# placa2caras_CTO4.net
KiCad netlist of a schematic drawn in EAGLE
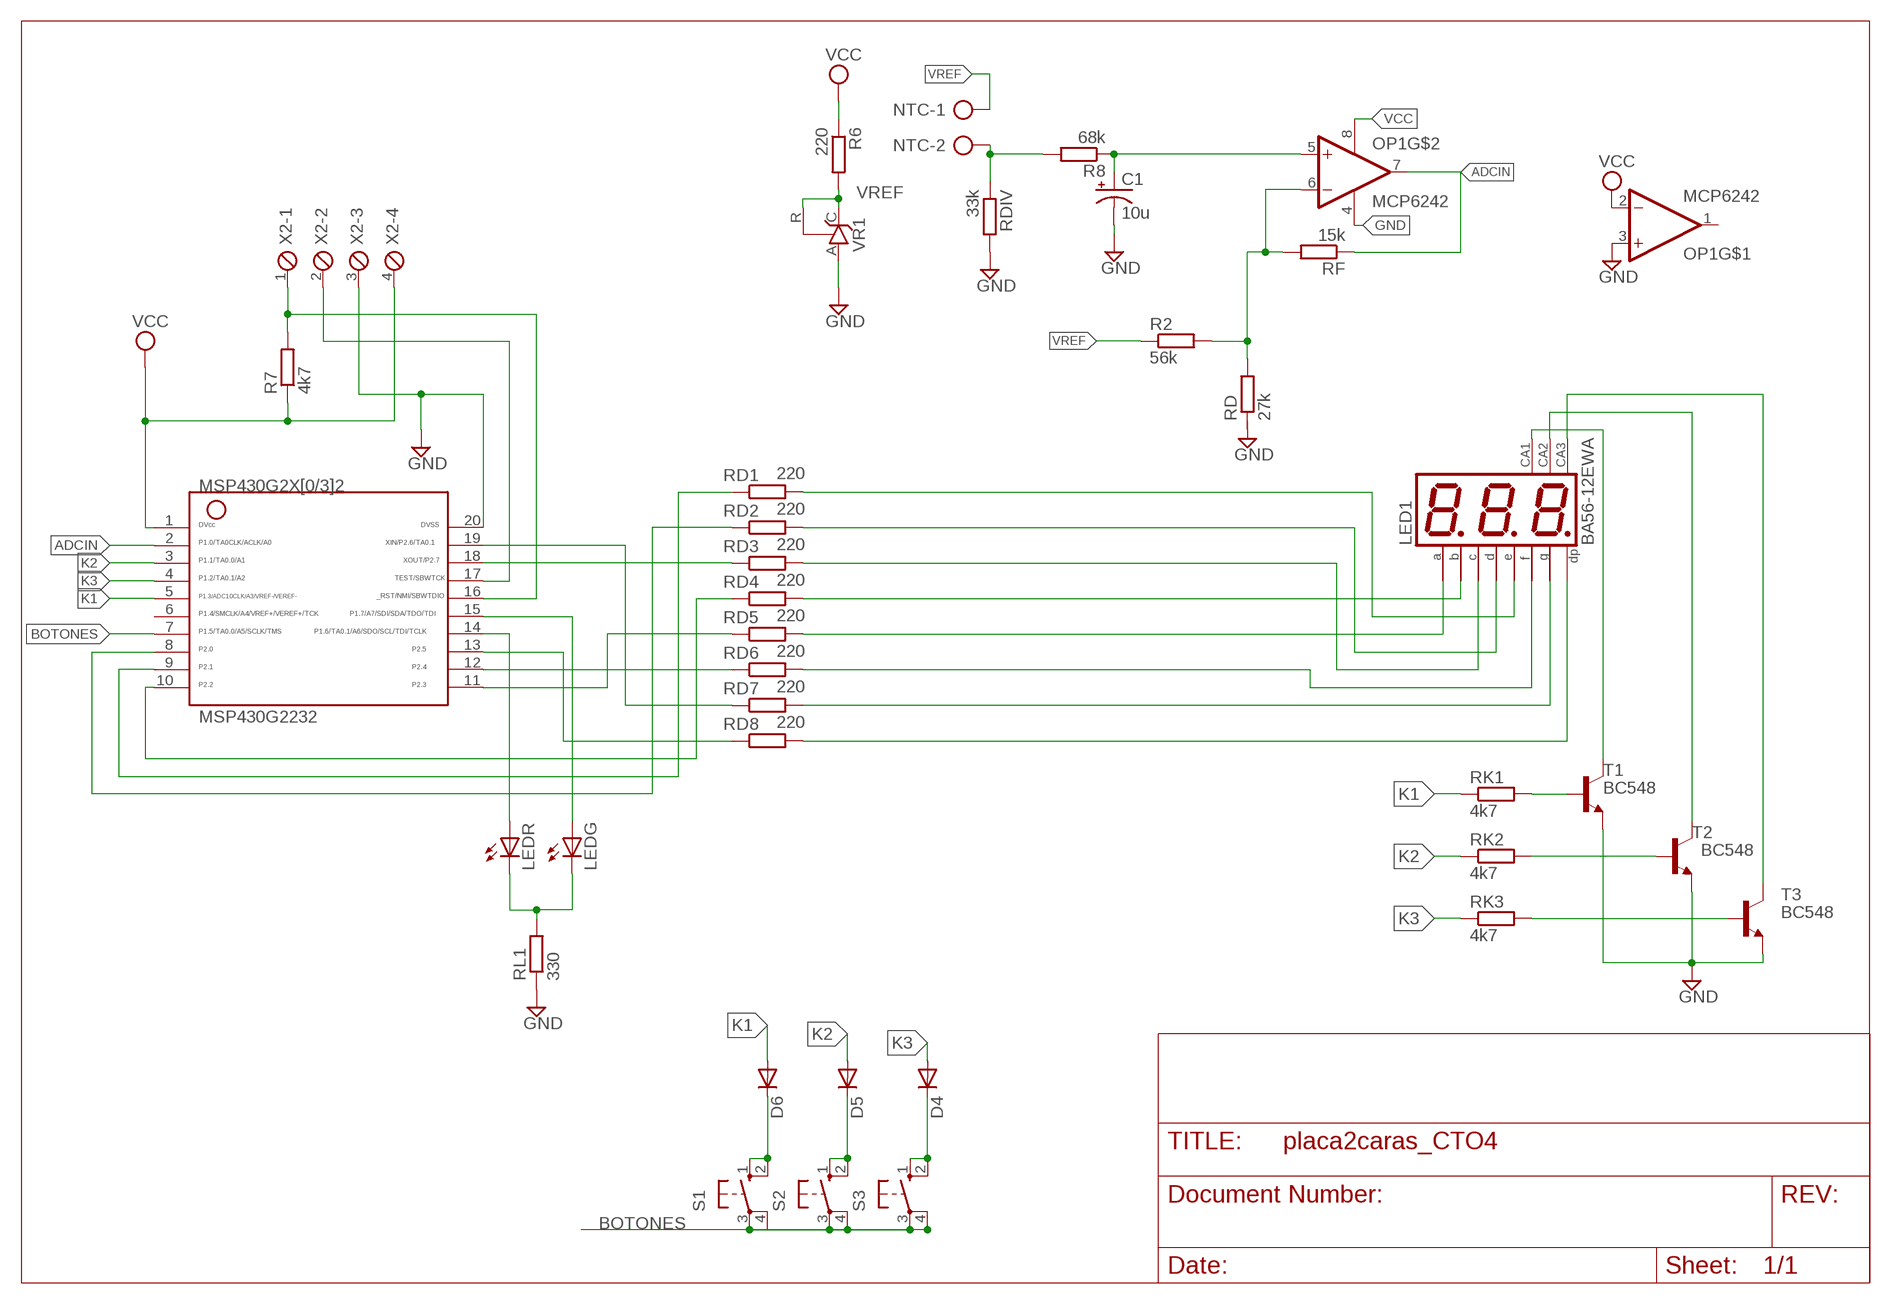
[diagram p0: schematic, sheet 1]

(export (version "E")
  (design (tool "Eeschema 10.0.6"))
  (components
    (comp (ref "C1")
      (value "10u")
      (footprint "eagle-import:E2,5-6E")
      (libsource (lib "eagle-import") (part "CPOL-USE2,5-6E"))
    )
    (comp (ref "D4")
      (value "1N4148DO35-10")
      (footprint "eagle-import:DO35-10")
      (libsource (lib "eagle-import") (part "1N4148DO35-10"))
    )
    (comp (ref "D5")
      (value "1N4148DO35-10")
      (footprint "eagle-import:DO35-10")
      (libsource (lib "eagle-import") (part "1N4148DO35-10"))
    )
    (comp (ref "D6")
      (value "1N4148DO35-10")
      (footprint "eagle-import:DO35-10")
      (libsource (lib "eagle-import") (part "1N4148DO35-10"))
    )
    (comp (ref "LED1")
      (value "BA56-12EWA")
      (footprint "eagle-import:BX56-12")
      (libsource (lib "eagle-import") (part "B?56-12WAAE"))
    )
    (comp (ref "LEDG")
      (value "LED5MM")
      (footprint "eagle-import:LED5MM")
      (libsource (lib "eagle-import") (part "LED5MM"))
    )
    (comp (ref "LEDR")
      (value "LED5MM")
      (footprint "eagle-import:LED5MM")
      (libsource (lib "eagle-import") (part "LED5MM"))
    )
    (comp (ref "MSP430G2232")
      (value "G2X[0/3]2---N20")
      (footprint "eagle-import:N20")
      (libsource (lib "eagle-import") (part "G2X[0/3]2---N20"))
    )
    (comp (ref "NTC")
      (value "AK500/2")
      (footprint "eagle-import:AK500_2")
      (libsource (lib "eagle-import") (part "AK500/2"))
    )
    (comp (ref "OP1")
      (value "MCP6242")
      (footprint "eagle-import:DIL8_MOD")
      (libsource (lib "eagle-import") (part "MCP6242CONPADGORDO"))
    )
    (comp (ref "R2")
      (value "56k")
      (footprint "eagle-import:0207_10")
      (libsource (lib "eagle-import") (part "resistor_mod2_R-EU_0207/10"))
    )
    (comp (ref "R6")
      (value "220")
      (footprint "eagle-import:0207_10")
      (libsource (lib "eagle-import") (part "resistor_mod2_R-EU_0207/10"))
    )
    (comp (ref "R7")
      (value "4k7")
      (footprint "eagle-import:0207_10")
      (libsource (lib "eagle-import") (part "resistor_mod2_R-EU_0207/10"))
    )
    (comp (ref "R8")
      (value "68k")
      (footprint "eagle-import:0207_10")
      (libsource (lib "eagle-import") (part "resistor_mod2_R-EU_0207/10"))
    )
    (comp (ref "RD")
      (value "27k")
      (footprint "eagle-import:0207_10")
      (libsource (lib "eagle-import") (part "resistor_mod2_R-EU_0207/10"))
    )
    (comp (ref "RD1")
      (value "220")
      (footprint "eagle-import:0207_10")
      (libsource (lib "eagle-import") (part "resistor_mod2_R-EU_0207/10"))
    )
    (comp (ref "RD2")
      (value "220")
      (footprint "eagle-import:0207_10")
      (libsource (lib "eagle-import") (part "resistor_mod2_R-EU_0207/10"))
    )
    (comp (ref "RD3")
      (value "220")
      (footprint "eagle-import:0207_10")
      (libsource (lib "eagle-import") (part "resistor_mod2_R-EU_0207/10"))
    )
    (comp (ref "RD4")
      (value "220")
      (footprint "eagle-import:0207_10")
      (libsource (lib "eagle-import") (part "resistor_mod2_R-EU_0207/10"))
    )
    (comp (ref "RD5")
      (value "220")
      (footprint "eagle-import:0207_10")
      (libsource (lib "eagle-import") (part "resistor_mod2_R-EU_0207/10"))
    )
    (comp (ref "RD6")
      (value "220")
      (footprint "eagle-import:0207_10")
      (libsource (lib "eagle-import") (part "resistor_mod2_R-EU_0207/10"))
    )
    (comp (ref "RD7")
      (value "220")
      (footprint "eagle-import:0207_10")
      (libsource (lib "eagle-import") (part "resistor_mod2_R-EU_0207/10"))
    )
    (comp (ref "RD8")
      (value "220")
      (footprint "eagle-import:0207_10")
      (libsource (lib "eagle-import") (part "resistor_mod2_R-EU_0207/10"))
    )
    (comp (ref "RDIV")
      (value "33k")
      (footprint "eagle-import:0207_10")
      (libsource (lib "eagle-import") (part "resistor_mod2_R-EU_0207/10"))
    )
    (comp (ref "RF")
      (value "15k")
      (footprint "eagle-import:0207_10")
      (libsource (lib "eagle-import") (part "resistor_mod2_R-EU_0207/10"))
    )
    (comp (ref "RK1")
      (value "4k7")
      (footprint "eagle-import:0207_10")
      (libsource (lib "eagle-import") (part "resistor_mod2_R-EU_0207/10"))
    )
    (comp (ref "RK2")
      (value "4k7")
      (footprint "eagle-import:0207_10")
      (libsource (lib "eagle-import") (part "resistor_mod2_R-EU_0207/10"))
    )
    (comp (ref "RK3")
      (value "4k7")
      (footprint "eagle-import:0207_10")
      (libsource (lib "eagle-import") (part "resistor_mod2_R-EU_0207/10"))
    )
    (comp (ref "RL1")
      (value "330")
      (footprint "eagle-import:0207_10")
      (libsource (lib "eagle-import") (part "R-EU_0207/10"))
    )
    (comp (ref "S1")
      (value "10-XX")
      (footprint "eagle-import:B3F-10XX")
      (fields (field (name "MPN") "B3F-1000"))
      (libsource (lib "eagle-import") (part "10-XX"))
    )
    (comp (ref "S2")
      (value "10-XX")
      (footprint "eagle-import:B3F-10XX")
      (fields (field (name "MPN") "B3F-1000"))
      (libsource (lib "eagle-import") (part "10-XX"))
    )
    (comp (ref "S3")
      (value "10-XX")
      (footprint "eagle-import:B3F-10XX")
      (fields (field (name "MPN") "B3F-1000"))
      (libsource (lib "eagle-import") (part "10-XX"))
    )
    (comp (ref "T1")
      (value "BC548")
      (footprint "eagle-import:TO92-EBC")
      (libsource (lib "eagle-import") (part "BC548"))
    )
    (comp (ref "T2")
      (value "BC548")
      (footprint "eagle-import:TO92-EBC")
      (libsource (lib "eagle-import") (part "BC548"))
    )
    (comp (ref "T3")
      (value "BC548")
      (footprint "eagle-import:TO92-EBC")
      (libsource (lib "eagle-import") (part "BC548"))
    )
    (comp (ref "VR1")
      (value "TL431CLP")
      (footprint "eagle-import:TO92-CLP")
      (libsource (lib "eagle-import") (part "TL431CLP"))
    )
    (comp (ref "X2")
      (value "MPT4")
      (footprint "eagle-import:4POL254")
      (libsource (lib "eagle-import") (part "MPT4"))
    )
  )
  (nets
    (net (code "1") (name "ADCIN") (class "Default")
      (node (ref "MSP430G2232") (pin "2") (pinfunction "2_2") (pintype "bidirectional"))
      (node (ref "OP1") (pin "7") (pinfunction "OUT_7") (pintype "output"))
      (node (ref "RF") (pin "1") (pinfunction "1_1") (pintype "passive"))
    )
    (net (code "2") (name "BOTONES") (class "Default")
      (node (ref "MSP430G2232") (pin "7") (pinfunction "7_7") (pintype "bidirectional"))
      (node (ref "S1") (pin "3") (pinfunction "P_3") (pintype "passive"))
      (node (ref "S1") (pin "4") (pinfunction "P1_4") (pintype "passive"))
      (node (ref "S2") (pin "3") (pinfunction "P_3") (pintype "passive"))
      (node (ref "S2") (pin "4") (pinfunction "P1_4") (pintype "passive"))
      (node (ref "S3") (pin "3") (pinfunction "P_3") (pintype "passive"))
      (node (ref "S3") (pin "4") (pinfunction "P1_4") (pintype "passive"))
    )
    (net (code "3") (name "GND") (class "Default")
      (node (ref "C1") (pin "-") (pinfunction "-_-") (pintype "passive"))
      (node (ref "MSP430G2232") (pin "20") (pinfunction "20_20") (pintype "bidirectional"))
      (node (ref "OP1") (pin "3") (pinfunction "+IN_3") (pintype "input"))
      (node (ref "OP1") (pin "4") (pinfunction "V-_4") (pintype "power_in"))
      (node (ref "RD") (pin "1") (pinfunction "1_1") (pintype "passive"))
      (node (ref "RDIV") (pin "2") (pinfunction "2_2") (pintype "passive"))
      (node (ref "RL1") (pin "1") (pinfunction "1_1") (pintype "passive"))
      (node (ref "T1") (pin "E") (pinfunction "E_E") (pintype "passive"))
      (node (ref "T2") (pin "E") (pinfunction "E_E") (pintype "passive"))
      (node (ref "T3") (pin "E") (pinfunction "E_E") (pintype "passive"))
      (node (ref "VR1") (pin "A") (pinfunction "A_A") (pintype "passive"))
      (node (ref "X2") (pin "3") (pinfunction "1_3") (pintype "passive"))
    )
    (net (code "4") (name "K1") (class "Default")
      (node (ref "D6") (pin "A") (pinfunction "A_A") (pintype "passive"))
      (node (ref "MSP430G2232") (pin "5") (pinfunction "5_5") (pintype "bidirectional"))
      (node (ref "RK1") (pin "1") (pinfunction "1_1") (pintype "passive"))
    )
    (net (code "5") (name "K2") (class "Default")
      (node (ref "D5") (pin "A") (pinfunction "A_A") (pintype "passive"))
      (node (ref "MSP430G2232") (pin "3") (pinfunction "3_3") (pintype "bidirectional"))
      (node (ref "RK2") (pin "1") (pinfunction "1_1") (pintype "passive"))
    )
    (net (code "6") (name "K3") (class "Default")
      (node (ref "D4") (pin "A") (pinfunction "A_A") (pintype "passive"))
      (node (ref "MSP430G2232") (pin "4") (pinfunction "4_4") (pintype "bidirectional"))
      (node (ref "RK3") (pin "1") (pinfunction "1_1") (pintype "passive"))
    )
    (net (code "7") (name "Net-(LED1-A)") (class "Default")
      (node (ref "LED1") (pin "11") (pinfunction "A_11") (pintype "passive"))
      (node (ref "RD5") (pin "2") (pinfunction "2_2") (pintype "passive"))
    )
    (net (code "8") (name "Net-(LED1-B)") (class "Default")
      (node (ref "LED1") (pin "7") (pinfunction "B_7") (pintype "passive"))
      (node (ref "RD4") (pin "2") (pinfunction "2_2") (pintype "passive"))
    )
    (net (code "9") (name "Net-(LED1-C)") (class "Default")
      (node (ref "LED1") (pin "4") (pinfunction "C_4") (pintype "passive"))
      (node (ref "RD3") (pin "2") (pinfunction "2_2") (pintype "passive"))
    )
    (net (code "10") (name "Net-(LED1-CA-Pad8)") (class "Default")
      (node (ref "LED1") (pin "8") (pinfunction "CA_8") (pintype "passive"))
      (node (ref "T3") (pin "C") (pinfunction "C_C") (pintype "passive"))
    )
    (net (code "11") (name "Net-(LED1-CA-Pad9)") (class "Default")
      (node (ref "LED1") (pin "9") (pinfunction "CA_9") (pintype "passive"))
      (node (ref "T2") (pin "C") (pinfunction "C_C") (pintype "passive"))
    )
    (net (code "12") (name "Net-(LED1-CA-Pad12)") (class "Default")
      (node (ref "LED1") (pin "12") (pinfunction "CA_12") (pintype "passive"))
      (node (ref "T1") (pin "C") (pinfunction "C_C") (pintype "passive"))
    )
    (net (code "13") (name "Net-(LED1-D)") (class "Default")
      (node (ref "LED1") (pin "2") (pinfunction "D_2") (pintype "passive"))
      (node (ref "RD2") (pin "2") (pinfunction "2_2") (pintype "passive"))
    )
    (net (code "14") (name "Net-(LED1-DP)") (class "Default")
      (node (ref "LED1") (pin "3") (pinfunction "DP_3") (pintype "passive"))
      (node (ref "RD8") (pin "2") (pinfunction "2_2") (pintype "passive"))
    )
    (net (code "15") (name "Net-(LED1-E)") (class "Default")
      (node (ref "LED1") (pin "1") (pinfunction "E_1") (pintype "passive"))
      (node (ref "RD1") (pin "2") (pinfunction "2_2") (pintype "passive"))
    )
    (net (code "16") (name "Net-(LED1-F)") (class "Default")
      (node (ref "LED1") (pin "10") (pinfunction "F_10") (pintype "passive"))
      (node (ref "RD6") (pin "2") (pinfunction "2_2") (pintype "passive"))
    )
    (net (code "17") (name "Net-(LED1-G)") (class "Default")
      (node (ref "LED1") (pin "5") (pinfunction "G_5") (pintype "passive"))
      (node (ref "RD7") (pin "2") (pinfunction "2_2") (pintype "passive"))
    )
    (net (code "18") (name "Net-(LEDG-C)") (class "Default")
      (node (ref "LEDG") (pin "K") (pinfunction "C_K") (pintype "passive"))
      (node (ref "LEDR") (pin "K") (pinfunction "C_K") (pintype "passive"))
      (node (ref "RL1") (pin "2") (pinfunction "2_2") (pintype "passive"))
    )
    (net (code "19") (name "Net-(LEDG-PadA)") (class "Default")
      (node (ref "LEDG") (pin "A") (pinfunction "A_A") (pintype "passive"))
      (node (ref "MSP430G2232") (pin "15") (pinfunction "15_15") (pintype "bidirectional"))
    )
    (net (code "20") (name "Net-(LEDR-PadA)") (class "Default")
      (node (ref "LEDR") (pin "A") (pinfunction "A_A") (pintype "passive"))
      (node (ref "MSP430G2232") (pin "14") (pinfunction "14_14") (pintype "bidirectional"))
    )
    (net (code "21") (name "Net-(MSP430G2232-Pad8)") (class "Default")
      (node (ref "MSP430G2232") (pin "8") (pinfunction "8_8") (pintype "bidirectional"))
      (node (ref "RD2") (pin "1") (pinfunction "1_1") (pintype "passive"))
    )
    (net (code "22") (name "Net-(MSP430G2232-Pad9)") (class "Default")
      (node (ref "MSP430G2232") (pin "9") (pinfunction "9_9") (pintype "bidirectional"))
      (node (ref "RD1") (pin "1") (pinfunction "1_1") (pintype "passive"))
    )
    (net (code "23") (name "Net-(MSP430G2232-Pad10)") (class "Default")
      (node (ref "MSP430G2232") (pin "10") (pinfunction "10_10") (pintype "bidirectional"))
      (node (ref "RD4") (pin "1") (pinfunction "1_1") (pintype "passive"))
    )
    (net (code "24") (name "Net-(MSP430G2232-Pad11)") (class "Default")
      (node (ref "MSP430G2232") (pin "11") (pinfunction "11_11") (pintype "bidirectional"))
      (node (ref "RD5") (pin "1") (pinfunction "1_1") (pintype "passive"))
    )
    (net (code "25") (name "Net-(MSP430G2232-Pad12)") (class "Default")
      (node (ref "MSP430G2232") (pin "12") (pinfunction "12_12") (pintype "bidirectional"))
      (node (ref "RD6") (pin "1") (pinfunction "1_1") (pintype "passive"))
    )
    (net (code "26") (name "Net-(MSP430G2232-Pad13)") (class "Default")
      (node (ref "MSP430G2232") (pin "13") (pinfunction "13_13") (pintype "bidirectional"))
      (node (ref "RD8") (pin "1") (pinfunction "1_1") (pintype "passive"))
    )
    (net (code "27") (name "Net-(MSP430G2232-Pad16)") (class "Default")
      (node (ref "MSP430G2232") (pin "16") (pinfunction "16_16") (pintype "bidirectional"))
      (node (ref "R7") (pin "2") (pinfunction "2_2") (pintype "passive"))
      (node (ref "X2") (pin "1") (pinfunction "1_1") (pintype "passive"))
    )
    (net (code "28") (name "Net-(MSP430G2232-Pad18)") (class "Default")
      (node (ref "MSP430G2232") (pin "18") (pinfunction "18_18") (pintype "bidirectional"))
      (node (ref "RD3") (pin "1") (pinfunction "1_1") (pintype "passive"))
    )
    (net (code "29") (name "Net-(MSP430G2232-Pad19)") (class "Default")
      (node (ref "MSP430G2232") (pin "19") (pinfunction "19_19") (pintype "bidirectional"))
      (node (ref "RD7") (pin "1") (pinfunction "1_1") (pintype "passive"))
    )
    (net (code "30") (name "Net-(NTCB-KL)") (class "Default")
      (node (ref "NTC") (pin "2") (pinfunction "KL_2") (pintype "passive"))
      (node (ref "R8") (pin "2") (pinfunction "2_2") (pintype "passive"))
      (node (ref "RDIV") (pin "1") (pinfunction "1_1") (pintype "passive"))
    )
    (net (code "31") (name "Net-(OP1B-+IN)") (class "Default")
      (node (ref "C1") (pin "+") (pinfunction "+_+") (pintype "passive"))
      (node (ref "OP1") (pin "5") (pinfunction "+IN_5") (pintype "input"))
      (node (ref "R8") (pin "1") (pinfunction "1_1") (pintype "passive"))
    )
    (net (code "32") (name "Net-(OP1B--IN)") (class "Default")
      (node (ref "OP1") (pin "6") (pinfunction "-IN_6") (pintype "input"))
      (node (ref "R2") (pin "2") (pinfunction "2_2") (pintype "passive"))
      (node (ref "RD") (pin "2") (pinfunction "2_2") (pintype "passive"))
      (node (ref "RF") (pin "2") (pinfunction "2_2") (pintype "passive"))
    )
    (net (code "33") (name "Net-(RK1-Pad2)") (class "Default")
      (node (ref "RK1") (pin "2") (pinfunction "2_2") (pintype "passive"))
      (node (ref "T1") (pin "B") (pinfunction "B_B") (pintype "passive"))
    )
    (net (code "34") (name "Net-(RK2-Pad2)") (class "Default")
      (node (ref "RK2") (pin "2") (pinfunction "2_2") (pintype "passive"))
      (node (ref "T2") (pin "B") (pinfunction "B_B") (pintype "passive"))
    )
    (net (code "35") (name "Net-(RK3-Pad2)") (class "Default")
      (node (ref "RK3") (pin "2") (pinfunction "2_2") (pintype "passive"))
      (node (ref "T3") (pin "B") (pinfunction "B_B") (pintype "passive"))
    )
    (net (code "36") (name "Net-(S1-S)") (class "Default")
      (node (ref "D6") (pin "C") (pinfunction "C_C") (pintype "passive"))
      (node (ref "S1") (pin "1") (pinfunction "S_1") (pintype "passive"))
      (node (ref "S1") (pin "2") (pinfunction "S1_2") (pintype "passive"))
    )
    (net (code "37") (name "Net-(S2-S)") (class "Default")
      (node (ref "D5") (pin "C") (pinfunction "C_C") (pintype "passive"))
      (node (ref "S2") (pin "1") (pinfunction "S_1") (pintype "passive"))
      (node (ref "S2") (pin "2") (pinfunction "S1_2") (pintype "passive"))
    )
    (net (code "38") (name "Net-(S3-S)") (class "Default")
      (node (ref "D4") (pin "C") (pinfunction "C_C") (pintype "passive"))
      (node (ref "S3") (pin "1") (pinfunction "S_1") (pintype "passive"))
      (node (ref "S3") (pin "2") (pinfunction "S1_2") (pintype "passive"))
    )
    (net (code "39") (name "Net-(X2B-1)") (class "Default")
      (node (ref "MSP430G2232") (pin "17") (pinfunction "17_17") (pintype "bidirectional"))
      (node (ref "X2") (pin "2") (pinfunction "1_2") (pintype "passive"))
    )
    (net (code "40") (name "VCC") (class "Default")
      (node (ref "MSP430G2232") (pin "1") (pinfunction "1_1") (pintype "bidirectional"))
      (node (ref "OP1") (pin "2") (pinfunction "-IN_2") (pintype "input"))
      (node (ref "OP1") (pin "8") (pinfunction "V+_8") (pintype "power_in"))
      (node (ref "R6") (pin "1") (pinfunction "1_1") (pintype "passive"))
      (node (ref "R7") (pin "1") (pinfunction "1_1") (pintype "passive"))
      (node (ref "X2") (pin "4") (pinfunction "1_4") (pintype "passive"))
    )
    (net (code "41") (name "VREF") (class "Default")
      (node (ref "NTC") (pin "1") (pinfunction "KL_1") (pintype "passive"))
      (node (ref "R2") (pin "1") (pinfunction "1_1") (pintype "passive"))
      (node (ref "R6") (pin "2") (pinfunction "2_2") (pintype "passive"))
      (node (ref "VR1") (pin "C") (pinfunction "C_C") (pintype "passive"))
      (node (ref "VR1") (pin "R") (pinfunction "R_R") (pintype "passive"))
    )
    (net (code "42") (name "unconnected-(MSP430G2232-Pad6)") (class "Default")
      (node (ref "MSP430G2232") (pin "6") (pinfunction "6_6") (pintype "bidirectional"))
    )
    (net (code "43") (name "unconnected-(OP1A-OUT-Pad1)") (class "Default")
      (node (ref "OP1") (pin "1") (pinfunction "OUT_1") (pintype "output"))
    )
  )
)
